# 2DD-20-mk-2_0_0.net
KiCad netlist of a schematic drawn in EAGLE
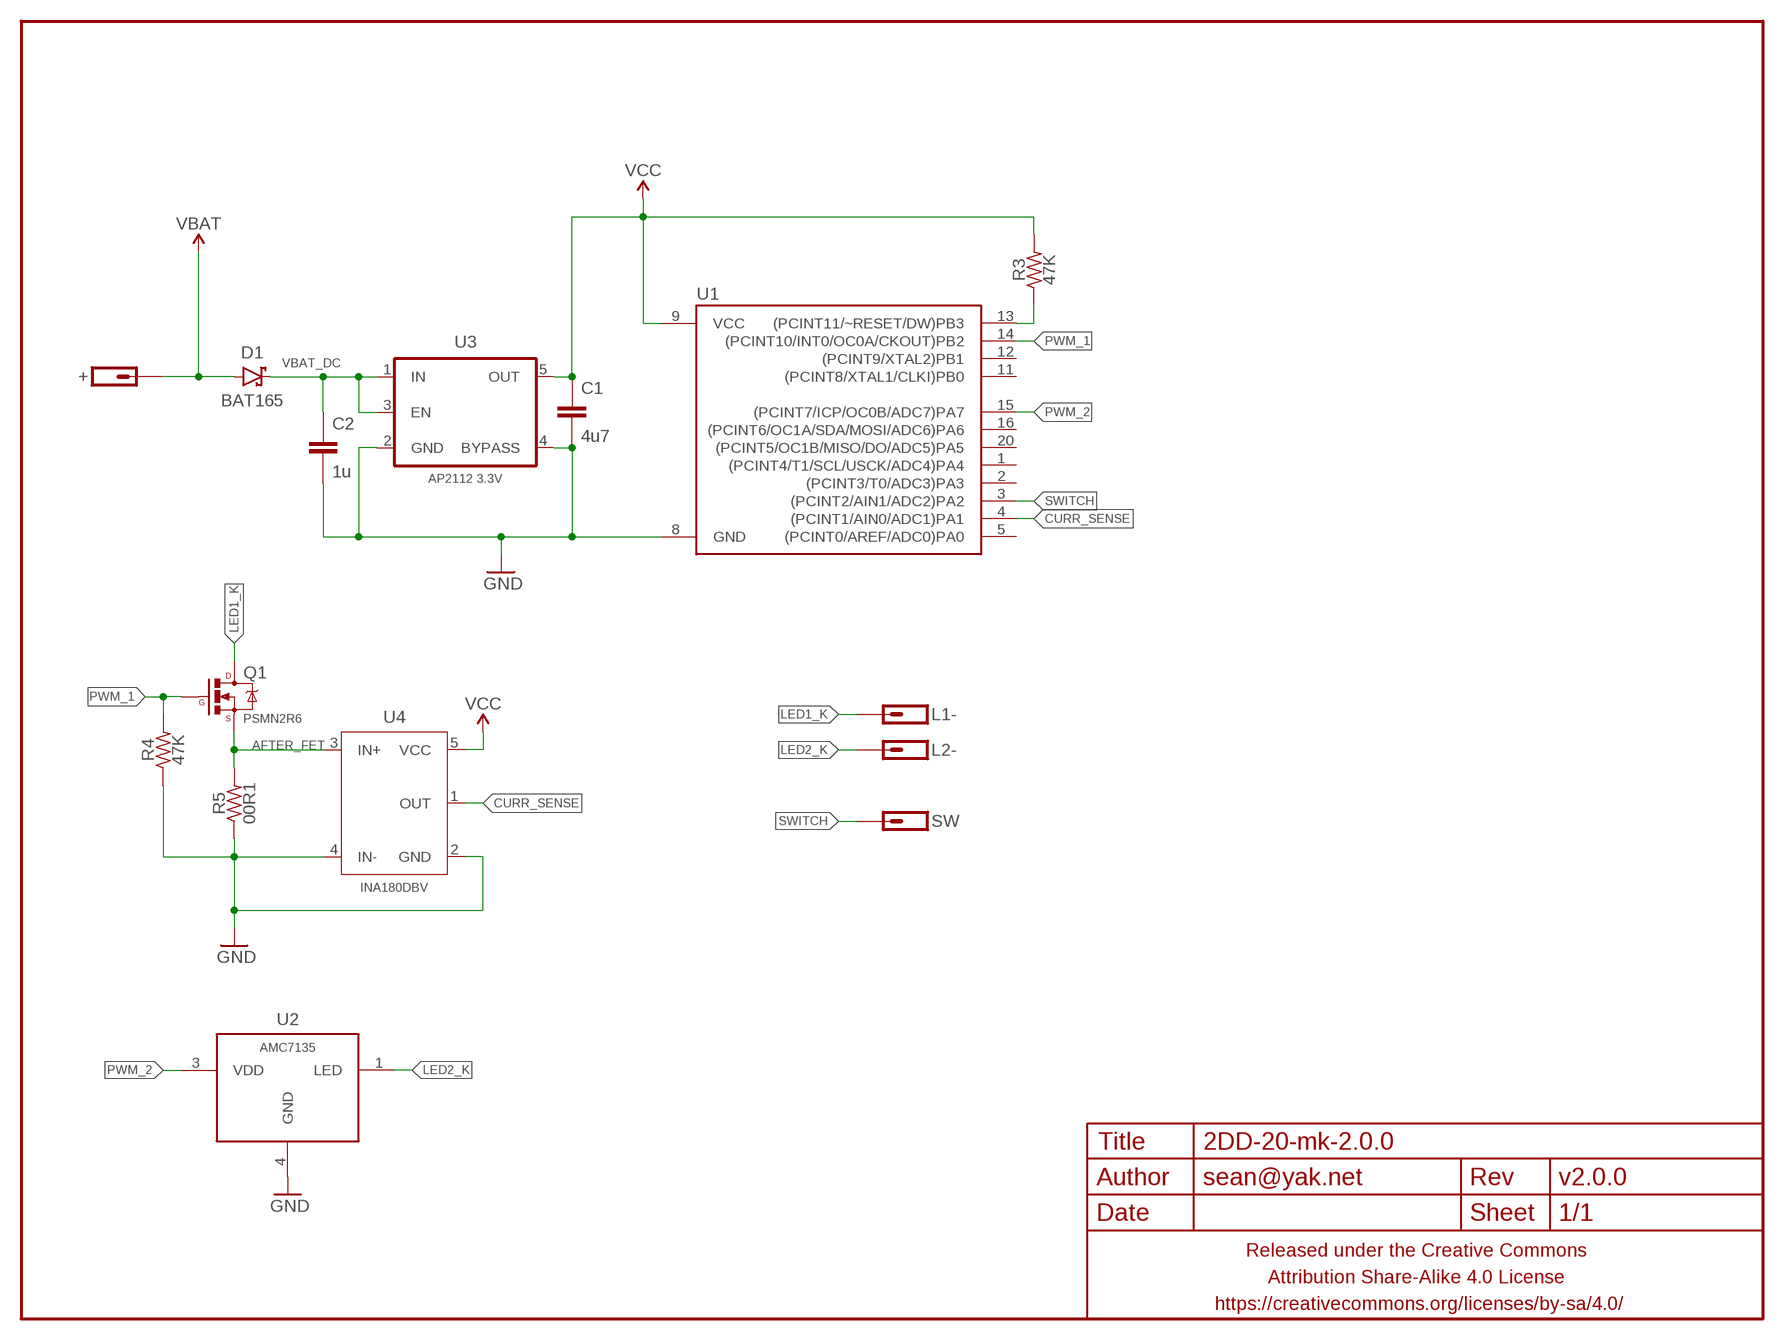
[diagram p0: schematic, sheet 1]

(export (version "E")
  (design (tool "Eeschema 10.0.6"))
  (components
    (comp (ref "+")
      (value "M01PTH-1MM-CIR-NS")
      (footprint "eagle-import:1X01-1MM-CIR-NS")
      (libsource (lib "eagle-import") (part "M01PTH-1MM-CIR-NS"))
    )
    (comp (ref "C1")
      (value "4u7")
      (footprint "eagle-import:C0603-TIGHTER")
      (libsource (lib "eagle-import") (part "CAPACITOR-CERAMICC0603-TIGHTER"))
    )
    (comp (ref "C2")
      (value "1u")
      (footprint "eagle-import:C0402")
      (libsource (lib "eagle-import") (part "CAPACITOR-CERAMICC0402"))
    )
    (comp (ref "D1")
      (value "BAT165")
      (footprint "eagle-import:SOD323-SCHOTTKY")
      (libsource (lib "eagle-import") (part "DIODE-SCHOTTKYSOD323"))
    )
    (comp (ref "FRAME1")
      (value "FRAME-LETTERNO_PACKAGE")
      (footprint "eagle-import:DUMMY")
      (fields (field (name "DESIGNER") "sean@yak.net") (field (name "VERSION") "v2.0.0"))
      (libsource (lib "eagle-import") (part "FRAME-LETTERNO_PACKAGE"))
    )
    (comp (ref "L1-")
      (value "M011X01-0.9MM-CIR")
      (footprint "eagle-import:1X01-0.9MM-CIR")
      (libsource (lib "eagle-import") (part "M011X01-0.9MM-CIR"))
    )
    (comp (ref "L2-")
      (value "M01PTH-0.8MM-CIR")
      (footprint "eagle-import:1X01-0.8MM-CIR")
      (libsource (lib "eagle-import") (part "M01PTH-0.8MM-CIR"))
    )
    (comp (ref "Q1")
      (value "PSMN2R6")
      (footprint "eagle-import:POWERPACK-SO-8")
      (libsource (lib "eagle-import") (part "MOSFET-NCHANNELSIR800DP"))
    )
    (comp (ref "R3")
      (value "47K")
      (footprint "eagle-import:R0402")
      (libsource (lib "eagle-import") (part "RESISTORR0402"))
    )
    (comp (ref "R4")
      (value "47K")
      (footprint "eagle-import:R0402")
      (libsource (lib "eagle-import") (part "RESISTORR0402"))
    )
    (comp (ref "R5")
      (value "00R1")
      (footprint "eagle-import:R1206")
      (libsource (lib "eagle-import") (part "RESISTORR1206"))
    )
    (comp (ref "SW")
      (value "M01SMD-0.8MM-DIA-NS")
      (footprint "eagle-import:1X01-SMD-0.8MM-DIA-NS")
      (libsource (lib "eagle-import") (part "M01SMD-0.8MM-DIA-NS"))
    )
    (comp (ref "U1")
      (value "ATTINY84ATTINY84-20MU")
      (footprint "eagle-import:QFN20")
      (libsource (lib "eagle-import") (part "ATTINY84ATTINY84-20MU"))
    )
    (comp (ref "U2")
      (value "AMC7135")
      (footprint "eagle-import:SOT89-NOTHERM-ROUNDED-LESS")
      (libsource (lib "eagle-import") (part "AMC7135SOT-89-NOTHERM-ROUNDED-LESS"))
    )
    (comp (ref "U3")
      (value "AP2112 3.3V")
      (footprint "eagle-import:SOT23-5")
      (libsource (lib "eagle-import") (part "V_REG_SOT-23-5AP2112"))
    )
    (comp (ref "U4")
      (value "INA180DBV")
      (footprint "eagle-import:SOT23-5")
      (libsource (lib "eagle-import") (part "INA180DBV"))
    )
  )
  (nets
    (net (code "1") (name "/AFTER_FET") (class "Default")
      (node (ref "Q1") (pin "1") (pinfunction "S_1") (pintype "passive"))
      (node (ref "Q1") (pin "2") (pinfunction "S_2") (pintype "passive"))
      (node (ref "Q1") (pin "3") (pinfunction "S_3") (pintype "passive"))
      (node (ref "R5") (pin "2") (pinfunction "2_2") (pintype "passive"))
      (node (ref "U4") (pin "3") (pinfunction "IN+_3") (pintype "bidirectional"))
    )
    (net (code "2") (name "/VBAT_DC") (class "Default")
      (node (ref "C2") (pin "1") (pinfunction "1_1") (pintype "passive"))
      (node (ref "D1") (pin "C") (pinfunction "C_C") (pintype "passive"))
      (node (ref "U3") (pin "1") (pinfunction "IN_1") (pintype "input"))
      (node (ref "U3") (pin "3") (pinfunction "EN_3") (pintype "input"))
    )
    (net (code "3") (name "CURR_SENSE") (class "Default")
      (node (ref "U1") (pin "4") (pinfunction "(PCINT1/AIN0/ADC1)PA1_4") (pintype "bidirectional"))
      (node (ref "U4") (pin "1") (pinfunction "OUT_1") (pintype "bidirectional"))
    )
    (net (code "4") (name "GND") (class "Default")
      (node (ref "C1") (pin "2") (pinfunction "2_2") (pintype "passive"))
      (node (ref "C2") (pin "2") (pinfunction "2_2") (pintype "passive"))
      (node (ref "R4") (pin "1") (pinfunction "1_1") (pintype "passive"))
      (node (ref "R5") (pin "1") (pinfunction "1_1") (pintype "passive"))
      (node (ref "U1") (pin "8") (pinfunction "GND_8") (pintype "bidirectional"))
      (node (ref "U2") (pin "4") (pinfunction "GND_4") (pintype "bidirectional"))
      (node (ref "U3") (pin "2") (pinfunction "GND_2") (pintype "input"))
      (node (ref "U3") (pin "4") (pinfunction "BYPASS_4") (pintype "input"))
      (node (ref "U4") (pin "2") (pinfunction "GND_2") (pintype "bidirectional"))
      (node (ref "U4") (pin "4") (pinfunction "IN-_4") (pintype "bidirectional"))
    )
    (net (code "5") (name "LED1_K") (class "Default")
      (node (ref "L1-") (pin "P$1") (pinfunction "1_P$1") (pintype "passive"))
      (node (ref "Q1") (pin "5678") (pinfunction "D_5678") (pintype "passive"))
    )
    (net (code "6") (name "LED2_K") (class "Default")
      (node (ref "L2-") (pin "1") (pinfunction "1_1") (pintype "passive"))
      (node (ref "U2") (pin "1") (pinfunction "LED_1") (pintype "bidirectional"))
    )
    (net (code "7") (name "Net-(U1-(PCINT11{slash}~{RESET{slash}DW})PB3)") (class "Default")
      (node (ref "R3") (pin "1") (pinfunction "1_1") (pintype "passive"))
      (node (ref "U1") (pin "13") (pinfunction "(PCINT11/~{RESET/DW})PB3_13") (pintype "bidirectional"))
    )
    (net (code "8") (name "PWM_1") (class "Default")
      (node (ref "Q1") (pin "4") (pinfunction "G_4") (pintype "passive"))
      (node (ref "R4") (pin "2") (pinfunction "2_2") (pintype "passive"))
      (node (ref "U1") (pin "14") (pinfunction "(PCINT10/INT0/OC0A/CKOUT)PB2_14") (pintype "bidirectional"))
    )
    (net (code "9") (name "PWM_2") (class "Default")
      (node (ref "U1") (pin "15") (pinfunction "(PCINT7/ICP/OC0B/ADC7)PA7_15") (pintype "bidirectional"))
      (node (ref "U2") (pin "3") (pinfunction "VDD_3") (pintype "bidirectional"))
    )
    (net (code "10") (name "SWITCH") (class "Default")
      (node (ref "SW") (pin "P$1") (pinfunction "1_P$1") (pintype "passive"))
      (node (ref "U1") (pin "3") (pinfunction "(PCINT2/AIN1/ADC2)PA2_3") (pintype "bidirectional"))
    )
    (net (code "11") (name "VBAT") (class "Default")
      (node (ref "+") (pin "1") (pinfunction "1_1") (pintype "passive"))
      (node (ref "D1") (pin "A") (pinfunction "A_A") (pintype "passive"))
    )
    (net (code "12") (name "VCC") (class "Default")
      (node (ref "C1") (pin "1") (pinfunction "1_1") (pintype "passive"))
      (node (ref "R3") (pin "2") (pinfunction "2_2") (pintype "passive"))
      (node (ref "U1") (pin "9") (pinfunction "VCC_9") (pintype "bidirectional"))
      (node (ref "U3") (pin "5") (pinfunction "OUT_5") (pintype "passive"))
      (node (ref "U4") (pin "5") (pinfunction "VCC_5") (pintype "bidirectional"))
    )
    (net (code "13") (name "unconnected-(U1-(PCINT0{slash}AREF{slash}ADC0)PA0-Pad5)") (class "Default")
      (node (ref "U1") (pin "5") (pinfunction "(PCINT0/AREF/ADC0)PA0_5") (pintype "bidirectional"))
    )
    (net (code "14") (name "unconnected-(U1-(PCINT3{slash}T0{slash}ADC3)PA3-Pad2)") (class "Default")
      (node (ref "U1") (pin "2") (pinfunction "(PCINT3/T0/ADC3)PA3_2") (pintype "bidirectional"))
    )
    (net (code "15") (name "unconnected-(U1-(PCINT4{slash}T1{slash}SCL{slash}USCK{slash}ADC4)PA4-Pad1)") (class "Default")
      (node (ref "U1") (pin "1") (pinfunction "(PCINT4/T1/SCL/USCK/ADC4)PA4_1") (pintype "bidirectional"))
    )
    (net (code "16") (name "unconnected-(U1-(PCINT5{slash}OC1B{slash}MISO{slash}DO{slash}ADC5)PA5-Pad20)") (class "Default")
      (node (ref "U1") (pin "20") (pinfunction "(PCINT5/OC1B/MISO/DO/ADC5)PA5_20") (pintype "bidirectional"))
    )
    (net (code "17") (name "unconnected-(U1-(PCINT6{slash}OC1A{slash}SDA{slash}MOSI{slash}ADC6)PA6-Pad16)") (class "Default")
      (node (ref "U1") (pin "16") (pinfunction "(PCINT6/OC1A/SDA/MOSI/ADC6)PA6_16") (pintype "bidirectional"))
    )
    (net (code "18") (name "unconnected-(U1-(PCINT8{slash}XTAL1{slash}CLKI)PB0-Pad11)") (class "Default")
      (node (ref "U1") (pin "11") (pinfunction "(PCINT8/XTAL1/CLKI)PB0_11") (pintype "bidirectional"))
    )
    (net (code "19") (name "unconnected-(U1-(PCINT9{slash}XTAL2)PB1-Pad12)") (class "Default")
      (node (ref "U1") (pin "12") (pinfunction "(PCINT9/XTAL2)PB1_12") (pintype "bidirectional"))
    )
  )
)
